# RasPi-BplusHAT.net
KiCad netlist of a schematic drawn in EAGLE
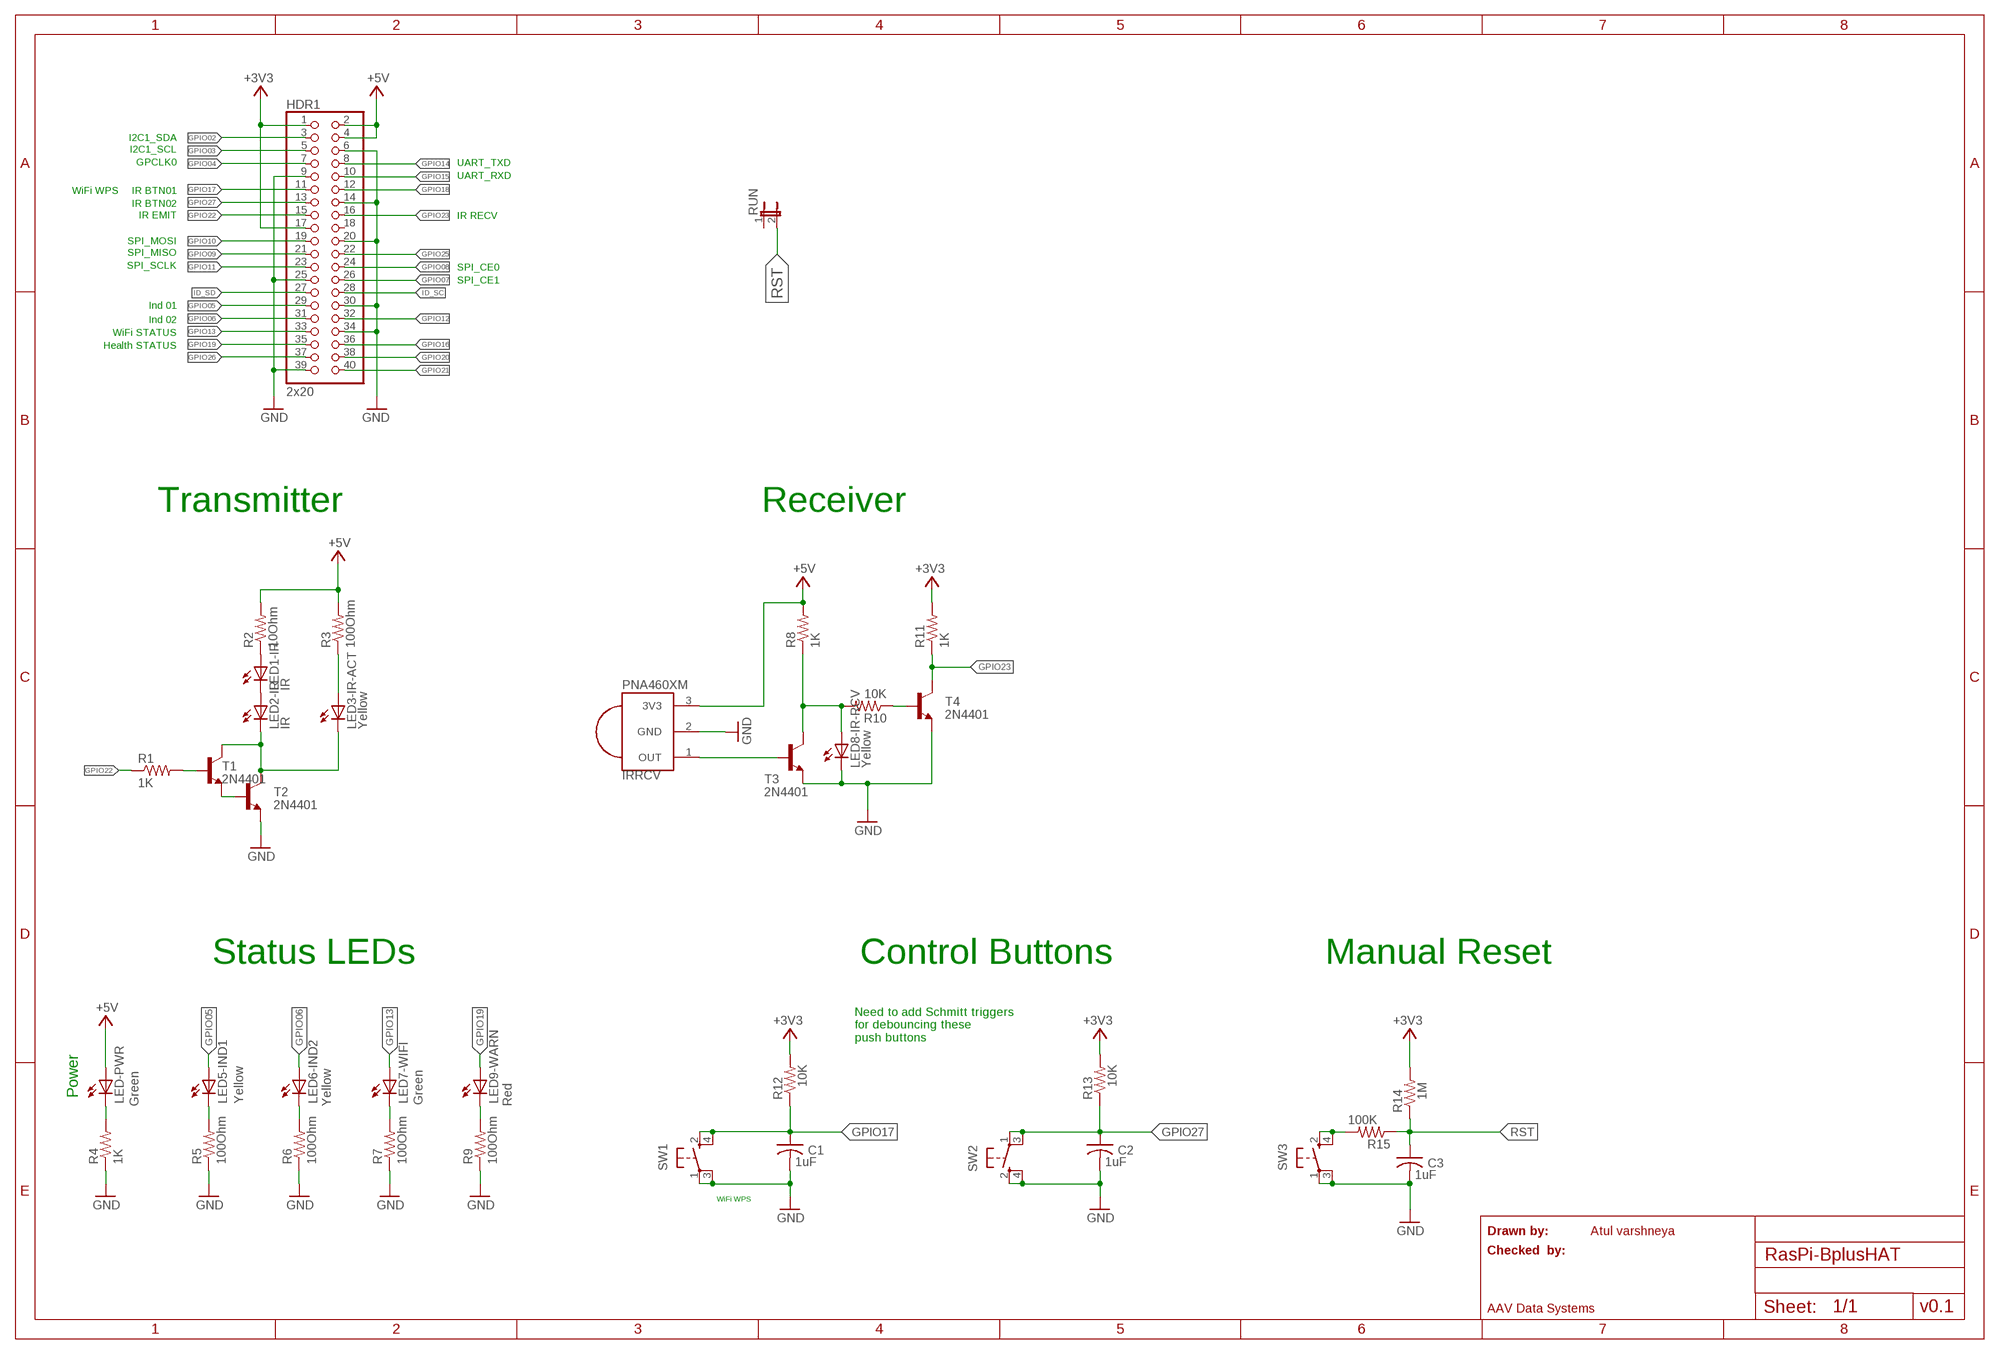
[diagram p0: schematic, sheet 1]

(export (version "E")
  (design (tool "Eeschema 10.0.6"))
  (components
    (comp (ref "C1")
      (value "1uF")
      (footprint "eagle-import:C0805")
      (fields (field (name "MPN") "MC0805B104K160CT"))
      (libsource (lib "eagle-import") (part "C-USC0805"))
    )
    (comp (ref "C2")
      (value "1uF")
      (footprint "eagle-import:C0805")
      (fields (field (name "MPN") "MC0805B104K160CT"))
      (libsource (lib "eagle-import") (part "C-USC0805"))
    )
    (comp (ref "C3")
      (value "1uF")
      (footprint "eagle-import:C0805")
      (fields (field (name "MPN") "MC0805B104K160CT"))
      (libsource (lib "eagle-import") (part "C-USC0805"))
    )
    (comp (ref "HDR1")
      (value "2x20")
      (footprint "eagle-import:2X20")
      (libsource (lib "eagle-import") (part "PINHD-2X20"))
    )
    (comp (ref "IRRCV")
      (value "PNA460XM")
      (footprint "eagle-import:PNA460XM")
      (fields (field (name "MPN") "TSOP38238"))
      (libsource (lib "eagle-import") (part "PNA460XM"))
    )
    (comp (ref "LED-PWR")
      (value "Green")
      (footprint "eagle-import:CHIPLED_0805")
      (fields (field (name "MPN") "150080GS75000"))
      (libsource (lib "eagle-import") (part "LEDCHIPLED_0805"))
    )
    (comp (ref "LED1-IR")
      (value "IR")
      (footprint "eagle-import:MICRO-SIDELED")
      (fields (field (name "MPN") "VSMB2943SLX01"))
      (libsource (lib "eagle-import") (part "LEDMICRO-SIDELED"))
    )
    (comp (ref "LED2-IR")
      (value "IR")
      (footprint "eagle-import:MICRO-SIDELED")
      (fields (field (name "MPN") "VSMB2943SLX01"))
      (libsource (lib "eagle-import") (part "LEDMICRO-SIDELED"))
    )
    (comp (ref "LED3-IR-ACT")
      (value "Yellow")
      (footprint "eagle-import:CHIPLED_0805")
      (fields (field (name "MPN") "150080YS75000"))
      (libsource (lib "eagle-import") (part "LEDCHIPLED_0805"))
    )
    (comp (ref "LED5-IND1")
      (value "Yellow")
      (footprint "eagle-import:CHIPLED_0805")
      (fields (field (name "MPN") "150080YS75000"))
      (libsource (lib "eagle-import") (part "LEDCHIPLED_0805"))
    )
    (comp (ref "LED6-IND2")
      (value "Yellow")
      (footprint "eagle-import:CHIPLED_0805")
      (fields (field (name "MPN") "150080YS75000"))
      (libsource (lib "eagle-import") (part "LEDCHIPLED_0805"))
    )
    (comp (ref "LED7-WIFI")
      (value "Green")
      (footprint "eagle-import:CHIPLED_0805")
      (fields (field (name "MPN") "150080GS75000"))
      (libsource (lib "eagle-import") (part "LEDCHIPLED_0805"))
    )
    (comp (ref "LED8-IR-RCV")
      (value "Yellow")
      (footprint "eagle-import:CHIPLED_0805")
      (fields (field (name "MPN") "150080YS75000"))
      (libsource (lib "eagle-import") (part "LEDCHIPLED_0805"))
    )
    (comp (ref "LED9-WARN")
      (value "Red")
      (footprint "eagle-import:CHIPLED_0805")
      (fields (field (name "MPN") "150080RS75000"))
      (libsource (lib "eagle-import") (part "LEDCHIPLED_0805"))
    )
    (comp (ref "R1")
      (value "1K")
      (footprint "eagle-import:R0805")
      (fields (field (name "MF") "VISHAY/DALE") (field (name "MPN") "CRCW08051K00FKEA"))
      (libsource (lib "eagle-import") (part "R-US_R0805"))
    )
    (comp (ref "R2")
      (value "10Ohm")
      (footprint "eagle-import:R0805")
      (fields (field (name "MF") "VISHAY/DALE") (field (name "MPN") "CRCW080510R0FKEA"))
      (libsource (lib "eagle-import") (part "R-US_R0805"))
    )
    (comp (ref "R3")
      (value "100Ohm")
      (footprint "eagle-import:R0805")
      (fields (field (name "MF") "VISHAY/DALE") (field (name "MPN") "CRCW0805100RFKEA"))
      (libsource (lib "eagle-import") (part "R-US_R0805"))
    )
    (comp (ref "R4")
      (value "1K")
      (footprint "eagle-import:R0805")
      (fields (field (name "MF") "VISHAY/DALE") (field (name "MPN") "CRCW08051K00FKEA"))
      (libsource (lib "eagle-import") (part "R-US_R0805"))
    )
    (comp (ref "R5")
      (value "100Ohm")
      (footprint "eagle-import:R0805")
      (fields (field (name "MF") "VISHAY/DALE") (field (name "MPN") "CRCW0805100RFKEA"))
      (libsource (lib "eagle-import") (part "R-US_R0805"))
    )
    (comp (ref "R6")
      (value "100Ohm")
      (footprint "eagle-import:R0805")
      (fields (field (name "MF") "VISHAY/DALE") (field (name "MPN") "CRCW0805100RFKEA"))
      (libsource (lib "eagle-import") (part "R-US_R0805"))
    )
    (comp (ref "R7")
      (value "100Ohm")
      (footprint "eagle-import:R0805")
      (fields (field (name "MF") "VISHAY/DALE") (field (name "MPN") "CRCW0805100RFKEA"))
      (libsource (lib "eagle-import") (part "R-US_R0805"))
    )
    (comp (ref "R8")
      (value "1K")
      (footprint "eagle-import:R0805")
      (fields (field (name "MF") "VISHAY/DALE") (field (name "MPN") "CRCW08051K00FKEA"))
      (libsource (lib "eagle-import") (part "R-US_R0805"))
    )
    (comp (ref "R9")
      (value "100Ohm")
      (footprint "eagle-import:R0805")
      (fields (field (name "MF") "VISHAY/DALE") (field (name "MPN") "CRCW0805100RFKEA"))
      (libsource (lib "eagle-import") (part "R-US_R0805"))
    )
    (comp (ref "R10")
      (value "10K")
      (footprint "eagle-import:R0805")
      (fields (field (name "MF") "VISHAY/DALE") (field (name "MPN") "CRCW080510K0FKEA"))
      (libsource (lib "eagle-import") (part "R-US_R0805"))
    )
    (comp (ref "R11")
      (value "1K")
      (footprint "eagle-import:R0805")
      (fields (field (name "MF") "VISHAY/DALE") (field (name "MPN") "CRCW08051K00FKEA"))
      (libsource (lib "eagle-import") (part "R-US_R0805"))
    )
    (comp (ref "R12")
      (value "10K")
      (footprint "eagle-import:R0805")
      (fields (field (name "MF") "VISHAY/DALE") (field (name "MPN") "CRCW080510K0FKEA"))
      (libsource (lib "eagle-import") (part "R-US_R0805"))
    )
    (comp (ref "R13")
      (value "10K")
      (footprint "eagle-import:R0805")
      (fields (field (name "MF") "VISHAY/DALE") (field (name "MPN") "CRCW080510K0FKEA"))
      (libsource (lib "eagle-import") (part "R-US_R0805"))
    )
    (comp (ref "R14")
      (value "1M")
      (footprint "eagle-import:R0805")
      (fields (field (name "MF") "VISHAY/DALE") (field (name "MPN") "CRCW080510K0FKEA"))
      (libsource (lib "eagle-import") (part "R-US_R0805"))
    )
    (comp (ref "R15")
      (value "100K")
      (footprint "eagle-import:R0805")
      (fields (field (name "MF") "VISHAY/DALE") (field (name "MPN") "CRCW080510K0FKEA"))
      (libsource (lib "eagle-import") (part "R-US_R0805"))
    )
    (comp (ref "RUN")
      (value "JP1E")
      (footprint "eagle-import:JP1")
      (fields (field (name "MPN") "2211S-02G"))
      (libsource (lib "eagle-import") (part "JP1E"))
    )
    (comp (ref "SW1")
      (value "SPST_TACT-KMR2")
      (footprint "eagle-import:KMR2")
      (libsource (lib "eagle-import") (part "SPST_TACT-KMR2"))
    )
    (comp (ref "SW2")
      (value "SPST_TACT-KMR2")
      (footprint "eagle-import:KMR2")
      (libsource (lib "eagle-import") (part "SPST_TACT-KMR2"))
    )
    (comp (ref "SW3")
      (value "SPST_TACT-KMR2")
      (footprint "eagle-import:KMR2")
      (libsource (lib "eagle-import") (part "SPST_TACT-KMR2"))
    )
    (comp (ref "T1")
      (value "2N4401")
      (footprint "eagle-import:SOT23-BEC")
      (fields (field (name "MPN") "MMBT4401-TP"))
      (libsource (lib "eagle-import") (part "transistor-neu-to92_-NPN-SOT23-BECMMBT4401LT1"))
    )
    (comp (ref "T2")
      (value "2N4401")
      (footprint "eagle-import:SOT23-BEC")
      (fields (field (name "MPN") "MMBT4401-TP"))
      (libsource (lib "eagle-import") (part "transistor-neu-to92_-NPN-SOT23-BECMMBT4401LT1"))
    )
    (comp (ref "T3")
      (value "2N4401")
      (footprint "eagle-import:SOT23-BEC")
      (fields (field (name "MPN") "MMBT4401-TP"))
      (libsource (lib "eagle-import") (part "-NPN-SOT23-BECMMBT4401LT1"))
    )
    (comp (ref "T4")
      (value "2N4401")
      (footprint "eagle-import:SOT23-BEC")
      (fields (field (name "MPN") "MMBT4401-TP"))
      (libsource (lib "eagle-import") (part "-NPN-SOT23-BECMMBT4401LT1"))
    )
  )
  (nets
    (net (code "1") (name "+3V3") (class "Default")
      (node (ref "HDR1") (pin "1") (pinfunction "1_1") (pintype "passive"))
      (node (ref "HDR1") (pin "17") (pinfunction "17_17") (pintype "passive"))
      (node (ref "R11") (pin "2") (pinfunction "2_2") (pintype "passive"))
      (node (ref "R12") (pin "2") (pinfunction "2_2") (pintype "passive"))
      (node (ref "R13") (pin "2") (pinfunction "2_2") (pintype "passive"))
      (node (ref "R14") (pin "2") (pinfunction "2_2") (pintype "passive"))
    )
    (net (code "2") (name "+5V") (class "Default")
      (node (ref "HDR1") (pin "2") (pinfunction "2_2") (pintype "passive"))
      (node (ref "HDR1") (pin "4") (pinfunction "4_4") (pintype "passive"))
      (node (ref "IRRCV") (pin "3") (pinfunction "3V3_3") (pintype "power_in"))
      (node (ref "LED-PWR") (pin "A") (pinfunction "A_A") (pintype "passive"))
      (node (ref "R2") (pin "2") (pinfunction "2_2") (pintype "passive"))
      (node (ref "R3") (pin "2") (pinfunction "2_2") (pintype "passive"))
      (node (ref "R8") (pin "2") (pinfunction "2_2") (pintype "passive"))
    )
    (net (code "3") (name "GND") (class "Default")
      (node (ref "C1") (pin "2") (pinfunction "2_2") (pintype "passive"))
      (node (ref "C2") (pin "2") (pinfunction "2_2") (pintype "passive"))
      (node (ref "C3") (pin "2") (pinfunction "2_2") (pintype "passive"))
      (node (ref "HDR1") (pin "14") (pinfunction "14_14") (pintype "passive"))
      (node (ref "HDR1") (pin "20") (pinfunction "20_20") (pintype "passive"))
      (node (ref "HDR1") (pin "25") (pinfunction "25_25") (pintype "passive"))
      (node (ref "HDR1") (pin "30") (pinfunction "30_30") (pintype "passive"))
      (node (ref "HDR1") (pin "34") (pinfunction "34_34") (pintype "passive"))
      (node (ref "HDR1") (pin "39") (pinfunction "39_39") (pintype "passive"))
      (node (ref "HDR1") (pin "6") (pinfunction "6_6") (pintype "passive"))
      (node (ref "HDR1") (pin "9") (pinfunction "9_9") (pintype "passive"))
      (node (ref "IRRCV") (pin "2") (pinfunction "GND_2") (pintype "power_in"))
      (node (ref "LED8-IR-RCV") (pin "C") (pinfunction "C_C") (pintype "passive"))
      (node (ref "R4") (pin "1") (pinfunction "1_1") (pintype "passive"))
      (node (ref "R5") (pin "1") (pinfunction "1_1") (pintype "passive"))
      (node (ref "R6") (pin "1") (pinfunction "1_1") (pintype "passive"))
      (node (ref "R7") (pin "1") (pinfunction "1_1") (pintype "passive"))
      (node (ref "R9") (pin "1") (pinfunction "1_1") (pintype "passive"))
      (node (ref "SW1") (pin "1") (pinfunction "P_1") (pintype "passive"))
      (node (ref "SW1") (pin "3") (pinfunction "P1_3") (pintype "passive"))
      (node (ref "SW2") (pin "2") (pinfunction "S_2") (pintype "passive"))
      (node (ref "SW2") (pin "4") (pinfunction "S1_4") (pintype "passive"))
      (node (ref "SW3") (pin "1") (pinfunction "P_1") (pintype "passive"))
      (node (ref "SW3") (pin "3") (pinfunction "P1_3") (pintype "passive"))
      (node (ref "T2") (pin "E") (pinfunction "E_E") (pintype "passive"))
      (node (ref "T3") (pin "E") (pinfunction "E_E") (pintype "passive"))
      (node (ref "T4") (pin "E") (pinfunction "E_E") (pintype "passive"))
    )
    (net (code "4") (name "GPIO02") (class "Default")
      (node (ref "HDR1") (pin "3") (pinfunction "3_3") (pintype "passive"))
    )
    (net (code "5") (name "GPIO03") (class "Default")
      (node (ref "HDR1") (pin "5") (pinfunction "5_5") (pintype "passive"))
    )
    (net (code "6") (name "GPIO04") (class "Default")
      (node (ref "HDR1") (pin "7") (pinfunction "7_7") (pintype "passive"))
    )
    (net (code "7") (name "GPIO05") (class "Default")
      (node (ref "HDR1") (pin "29") (pinfunction "29_29") (pintype "passive"))
      (node (ref "LED5-IND1") (pin "A") (pinfunction "A_A") (pintype "passive"))
    )
    (net (code "8") (name "GPIO06") (class "Default")
      (node (ref "HDR1") (pin "31") (pinfunction "31_31") (pintype "passive"))
      (node (ref "LED6-IND2") (pin "A") (pinfunction "A_A") (pintype "passive"))
    )
    (net (code "9") (name "GPIO07") (class "Default")
      (node (ref "HDR1") (pin "26") (pinfunction "26_26") (pintype "passive"))
    )
    (net (code "10") (name "GPIO08") (class "Default")
      (node (ref "HDR1") (pin "24") (pinfunction "24_24") (pintype "passive"))
    )
    (net (code "11") (name "GPIO09") (class "Default")
      (node (ref "HDR1") (pin "21") (pinfunction "21_21") (pintype "passive"))
    )
    (net (code "12") (name "GPIO10") (class "Default")
      (node (ref "HDR1") (pin "19") (pinfunction "19_19") (pintype "passive"))
    )
    (net (code "13") (name "GPIO11") (class "Default")
      (node (ref "HDR1") (pin "23") (pinfunction "23_23") (pintype "passive"))
    )
    (net (code "14") (name "GPIO12") (class "Default")
      (node (ref "HDR1") (pin "32") (pinfunction "32_32") (pintype "passive"))
    )
    (net (code "15") (name "GPIO13") (class "Default")
      (node (ref "HDR1") (pin "33") (pinfunction "33_33") (pintype "passive"))
      (node (ref "LED7-WIFI") (pin "A") (pinfunction "A_A") (pintype "passive"))
    )
    (net (code "16") (name "GPIO14") (class "Default")
      (node (ref "HDR1") (pin "8") (pinfunction "8_8") (pintype "passive"))
    )
    (net (code "17") (name "GPIO15") (class "Default")
      (node (ref "HDR1") (pin "10") (pinfunction "10_10") (pintype "passive"))
    )
    (net (code "18") (name "GPIO16") (class "Default")
      (node (ref "HDR1") (pin "36") (pinfunction "36_36") (pintype "passive"))
    )
    (net (code "19") (name "GPIO17") (class "Default")
      (node (ref "C1") (pin "1") (pinfunction "1_1") (pintype "passive"))
      (node (ref "HDR1") (pin "11") (pinfunction "11_11") (pintype "passive"))
      (node (ref "R12") (pin "1") (pinfunction "1_1") (pintype "passive"))
      (node (ref "SW1") (pin "2") (pinfunction "S_2") (pintype "passive"))
      (node (ref "SW1") (pin "4") (pinfunction "S1_4") (pintype "passive"))
    )
    (net (code "20") (name "GPIO18") (class "Default")
      (node (ref "HDR1") (pin "12") (pinfunction "12_12") (pintype "passive"))
    )
    (net (code "21") (name "GPIO19") (class "Default")
      (node (ref "HDR1") (pin "35") (pinfunction "35_35") (pintype "passive"))
      (node (ref "LED9-WARN") (pin "A") (pinfunction "A_A") (pintype "passive"))
    )
    (net (code "22") (name "GPIO20") (class "Default")
      (node (ref "HDR1") (pin "38") (pinfunction "38_38") (pintype "passive"))
    )
    (net (code "23") (name "GPIO21") (class "Default")
      (node (ref "HDR1") (pin "40") (pinfunction "40_40") (pintype "passive"))
    )
    (net (code "24") (name "GPIO22") (class "Default")
      (node (ref "HDR1") (pin "15") (pinfunction "15_15") (pintype "passive"))
      (node (ref "R1") (pin "1") (pinfunction "1_1") (pintype "passive"))
    )
    (net (code "25") (name "GPIO23") (class "Default")
      (node (ref "HDR1") (pin "16") (pinfunction "16_16") (pintype "passive"))
      (node (ref "R11") (pin "1") (pinfunction "1_1") (pintype "passive"))
      (node (ref "T4") (pin "C") (pinfunction "C_C") (pintype "passive"))
    )
    (net (code "26") (name "GPIO25") (class "Default")
      (node (ref "HDR1") (pin "22") (pinfunction "22_22") (pintype "passive"))
    )
    (net (code "27") (name "GPIO26") (class "Default")
      (node (ref "HDR1") (pin "37") (pinfunction "37_37") (pintype "passive"))
    )
    (net (code "28") (name "GPIO27") (class "Default")
      (node (ref "C2") (pin "1") (pinfunction "1_1") (pintype "passive"))
      (node (ref "HDR1") (pin "13") (pinfunction "13_13") (pintype "passive"))
      (node (ref "R13") (pin "1") (pinfunction "1_1") (pintype "passive"))
      (node (ref "SW2") (pin "1") (pinfunction "P_1") (pintype "passive"))
      (node (ref "SW2") (pin "3") (pinfunction "P1_3") (pintype "passive"))
    )
    (net (code "29") (name "ID_SC") (class "Default")
      (node (ref "HDR1") (pin "28") (pinfunction "28_28") (pintype "passive"))
    )
    (net (code "30") (name "ID_SD") (class "Default")
      (node (ref "HDR1") (pin "27") (pinfunction "27_27") (pintype "passive"))
    )
    (net (code "31") (name "Net-(IRRCV-OUT)") (class "Default")
      (node (ref "IRRCV") (pin "1") (pinfunction "OUT_1") (pintype "output"))
      (node (ref "T3") (pin "B") (pinfunction "B_B") (pintype "passive"))
    )
    (net (code "32") (name "Net-(LED-PWR-PadC)") (class "Default")
      (node (ref "LED-PWR") (pin "C") (pinfunction "C_C") (pintype "passive"))
      (node (ref "R4") (pin "2") (pinfunction "2_2") (pintype "passive"))
    )
    (net (code "33") (name "Net-(LED1-IR-PadA)") (class "Default")
      (node (ref "LED1-IR") (pin "A") (pinfunction "A_A") (pintype "passive"))
      (node (ref "R2") (pin "1") (pinfunction "1_1") (pintype "passive"))
    )
    (net (code "34") (name "Net-(LED1-IR-PadC)") (class "Default")
      (node (ref "LED1-IR") (pin "C") (pinfunction "C_C") (pintype "passive"))
      (node (ref "LED2-IR") (pin "A") (pinfunction "A_A") (pintype "passive"))
    )
    (net (code "35") (name "Net-(LED2-IR-PadC)") (class "Default")
      (node (ref "LED2-IR") (pin "C") (pinfunction "C_C") (pintype "passive"))
      (node (ref "LED3-IR-ACT") (pin "C") (pinfunction "C_C") (pintype "passive"))
      (node (ref "T1") (pin "C") (pinfunction "C_C") (pintype "passive"))
      (node (ref "T2") (pin "C") (pinfunction "C_C") (pintype "passive"))
    )
    (net (code "36") (name "Net-(LED3-IR-ACT-PadA)") (class "Default")
      (node (ref "LED3-IR-ACT") (pin "A") (pinfunction "A_A") (pintype "passive"))
      (node (ref "R3") (pin "1") (pinfunction "1_1") (pintype "passive"))
    )
    (net (code "37") (name "Net-(LED5-IND1-PadC)") (class "Default")
      (node (ref "LED5-IND1") (pin "C") (pinfunction "C_C") (pintype "passive"))
      (node (ref "R5") (pin "2") (pinfunction "2_2") (pintype "passive"))
    )
    (net (code "38") (name "Net-(LED6-IND2-PadC)") (class "Default")
      (node (ref "LED6-IND2") (pin "C") (pinfunction "C_C") (pintype "passive"))
      (node (ref "R6") (pin "2") (pinfunction "2_2") (pintype "passive"))
    )
    (net (code "39") (name "Net-(LED7-WIFI-PadC)") (class "Default")
      (node (ref "LED7-WIFI") (pin "C") (pinfunction "C_C") (pintype "passive"))
      (node (ref "R7") (pin "2") (pinfunction "2_2") (pintype "passive"))
    )
    (net (code "40") (name "Net-(LED8-IR-RCV-PadA)") (class "Default")
      (node (ref "LED8-IR-RCV") (pin "A") (pinfunction "A_A") (pintype "passive"))
      (node (ref "R10") (pin "2") (pinfunction "2_2") (pintype "passive"))
      (node (ref "R8") (pin "1") (pinfunction "1_1") (pintype "passive"))
      (node (ref "T3") (pin "C") (pinfunction "C_C") (pintype "passive"))
    )
    (net (code "41") (name "Net-(LED9-WARN-PadC)") (class "Default")
      (node (ref "LED9-WARN") (pin "C") (pinfunction "C_C") (pintype "passive"))
      (node (ref "R9") (pin "2") (pinfunction "2_2") (pintype "passive"))
    )
    (net (code "42") (name "Net-(R1-Pad2)") (class "Default")
      (node (ref "R1") (pin "2") (pinfunction "2_2") (pintype "passive"))
      (node (ref "T1") (pin "B") (pinfunction "B_B") (pintype "passive"))
    )
    (net (code "43") (name "Net-(R10-Pad1)") (class "Default")
      (node (ref "R10") (pin "1") (pinfunction "1_1") (pintype "passive"))
      (node (ref "T4") (pin "B") (pinfunction "B_B") (pintype "passive"))
    )
    (net (code "44") (name "Net-(SW3-S)") (class "Default")
      (node (ref "R15") (pin "2") (pinfunction "2_2") (pintype "passive"))
      (node (ref "SW3") (pin "2") (pinfunction "S_2") (pintype "passive"))
      (node (ref "SW3") (pin "4") (pinfunction "S1_4") (pintype "passive"))
    )
    (net (code "45") (name "Net-(T1-PadE)") (class "Default")
      (node (ref "T1") (pin "E") (pinfunction "E_E") (pintype "passive"))
      (node (ref "T2") (pin "B") (pinfunction "B_B") (pintype "passive"))
    )
    (net (code "46") (name "RST") (class "Default")
      (node (ref "C3") (pin "1") (pinfunction "1_1") (pintype "passive"))
      (node (ref "R14") (pin "1") (pinfunction "1_1") (pintype "passive"))
      (node (ref "R15") (pin "1") (pinfunction "1_1") (pintype "passive"))
      (node (ref "RUN") (pin "2") (pinfunction "2_2") (pintype "passive"))
    )
    (net (code "47") (name "unconnected-(HDR1-Pad18)") (class "Default")
      (node (ref "HDR1") (pin "18") (pinfunction "18_18") (pintype "passive"))
    )
    (net (code "48") (name "unconnected-(RUN-Pad1)") (class "Default")
      (node (ref "RUN") (pin "1") (pinfunction "1_1") (pintype "passive"))
    )
  )
)
